# 9axe.net
KiCad netlist of a schematic drawn in Altium Designer
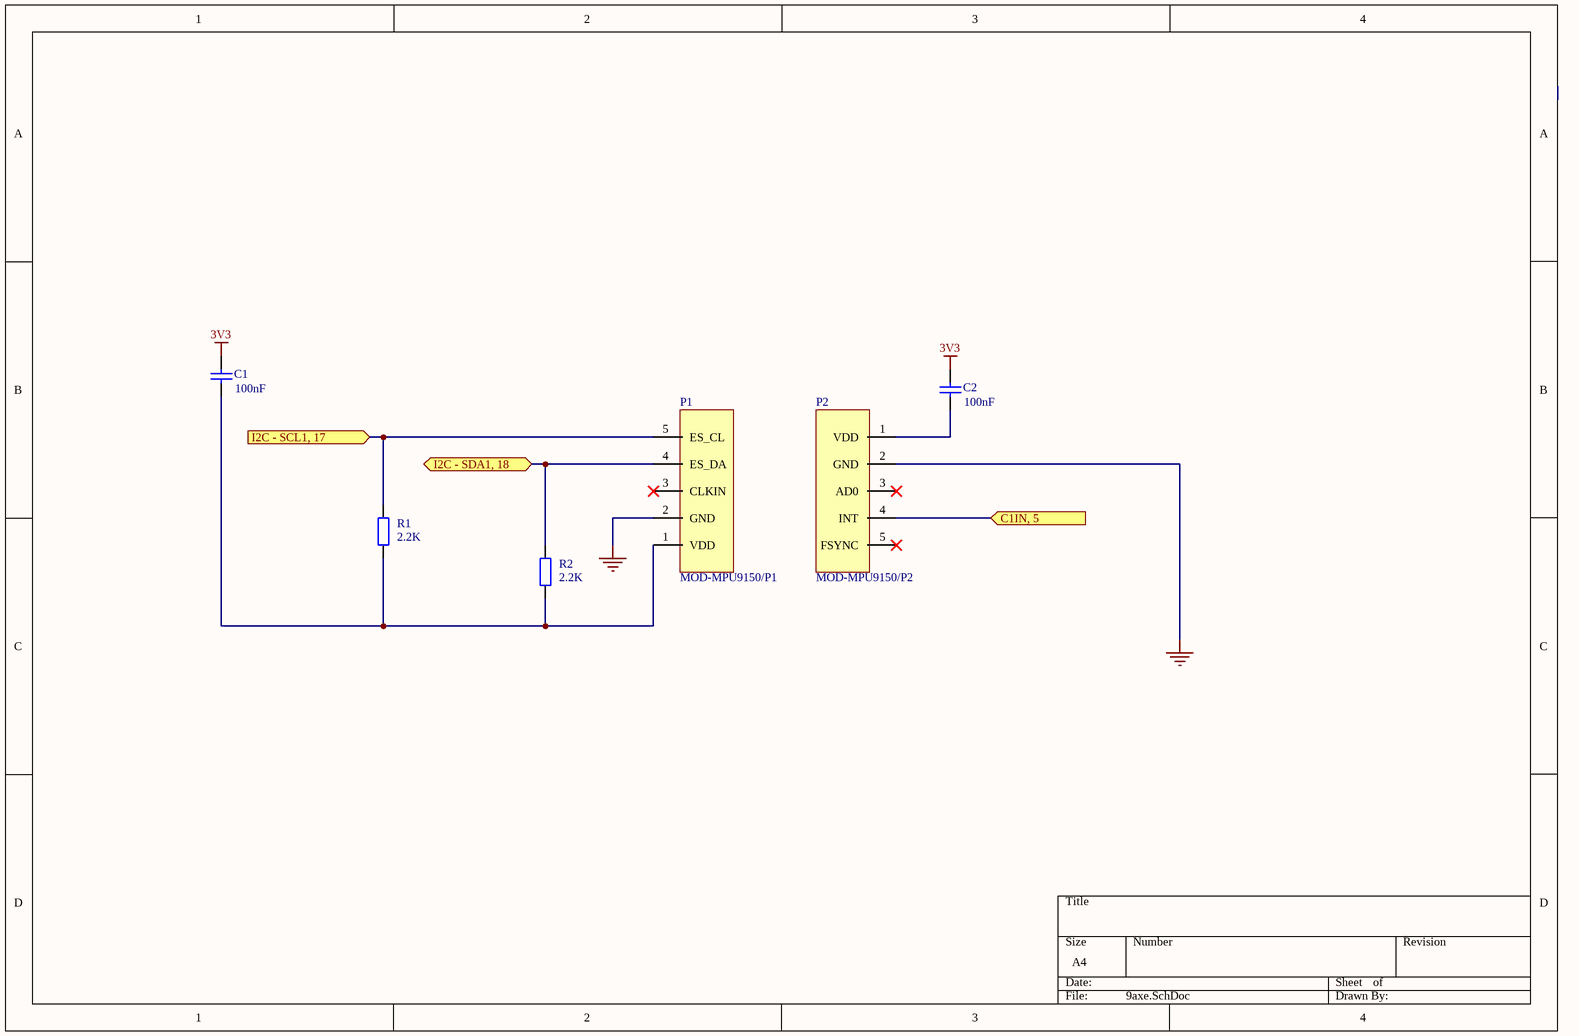
[diagram p0: 9axe.SchDoc]

(export (version "E")
  (design (tool "Eeschema 10.0.6"))
  (components
    (comp (ref "C1")
      (value "100nF")
      (footprint "RAD-0.3")
      (description "Capacitor")
      (fields (field (name "PUBLISHER") "Altium Limited"))
      (libsource (lib "Miscellaneous Devices") (part "Cap"))
    )
    (comp (ref "C2")
      (value "100nF")
      (footprint "RAD-0.3")
      (description "Capacitor")
      (fields (field (name "PUBLISHER") "Altium Limited"))
      (libsource (lib "Miscellaneous Devices") (part "Cap"))
    )
    (comp (ref "P1") (value "MOD-MPU9150/P1") (libsource (lib "Schematics_Library") (part "MOD-MPU9150/P1")))
    (comp (ref "P2") (value "MOD-MPU9150/P2") (libsource (lib "Schematics_Library") (part "MOD-MPU9150/P2")))
    (comp (ref "R1")
      (value "2.2K")
      (footprint "AXIAL-0.4")
      (description "Resistor")
      (fields (field (name "PUBLISHER") "Altium Limited"))
      (libsource (lib "") (part "Res2_1"))
    )
    (comp (ref "R2")
      (value "2.2K")
      (footprint "AXIAL-0.4")
      (description "Resistor")
      (fields (field (name "PUBLISHER") "Altium Limited"))
      (libsource (lib "Miscellaneous Devices") (part "Res2"))
    )
  )
  (nets
    (net (code "1") (name "/C1IN, 5") (class "Default")
      (node (ref "P2") (pin "4") (pinfunction "INT_4") (pintype "passive"))
    )
    (net (code "2") (name "/I2C - SCL1, 17") (class "Default")
      (node (ref "P1") (pin "5") (pinfunction "ES_CL_5") (pintype "passive"))
      (node (ref "R1") (pin "2") (pinfunction "2_2") (pintype "passive"))
    )
    (net (code "3") (name "/I2C - SDA1, 18") (class "Default")
      (node (ref "P1") (pin "4") (pinfunction "ES_DA_4") (pintype "passive"))
      (node (ref "R2") (pin "1") (pinfunction "1_1") (pintype "passive"))
    )
    (net (code "4") (name "3V3") (class "Default")
      (node (ref "C1") (pin "2") (pinfunction "2_2") (pintype "passive"))
      (node (ref "C2") (pin "2") (pinfunction "2_2") (pintype "passive"))
    )
    (net (code "5") (name "GND") (class "Default")
      (node (ref "P1") (pin "2") (pinfunction "GND_2") (pintype "passive"))
      (node (ref "P2") (pin "2") (pinfunction "GND_2") (pintype "passive"))
    )
    (net (code "6") (name "Net-(P1-VDD)") (class "Default")
      (node (ref "C1") (pin "1") (pinfunction "1_1") (pintype "passive"))
      (node (ref "P1") (pin "1") (pinfunction "VDD_1") (pintype "passive"))
      (node (ref "R1") (pin "1") (pinfunction "1_1") (pintype "passive"))
      (node (ref "R2") (pin "2") (pinfunction "2_2") (pintype "passive"))
    )
    (net (code "7") (name "Net-(P2-VDD)") (class "Default")
      (node (ref "C2") (pin "1") (pinfunction "1_1") (pintype "passive"))
      (node (ref "P2") (pin "1") (pinfunction "VDD_1") (pintype "passive"))
    )
    (net (code "8") (name "unconnected-(P1-CLKIN-Pad3)") (class "Default")
      (node (ref "P1") (pin "3") (pinfunction "CLKIN_3") (pintype "passive+no_connect"))
    )
    (net (code "9") (name "unconnected-(P2-AD0-Pad3)") (class "Default")
      (node (ref "P2") (pin "3") (pinfunction "AD0_3") (pintype "passive+no_connect"))
    )
    (net (code "10") (name "unconnected-(P2-FSYNC-Pad5)") (class "Default")
      (node (ref "P2") (pin "5") (pinfunction "FSYNC_5") (pintype "passive+no_connect"))
    )
  )
)
